# design.net
KiCad netlist of a schematic drawn in Altium Designer
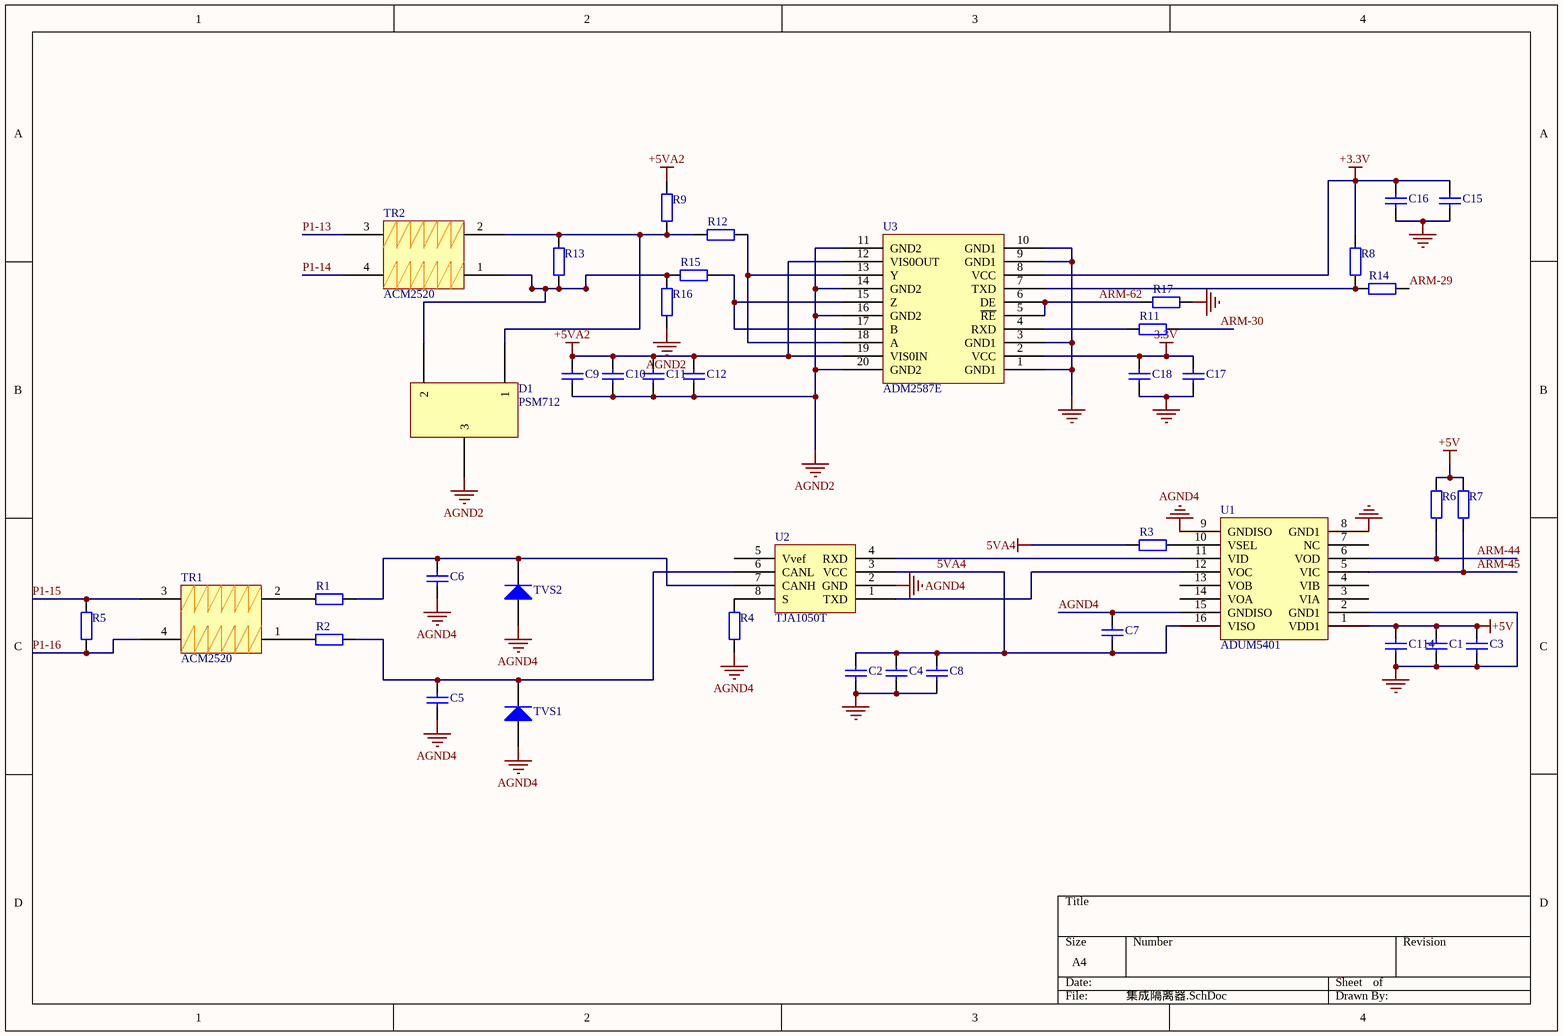
[diagram p0: 集成隔离器.SchDoc]

(export (version "E")
  (design (tool "Eeschema 10.0.6"))
  (components
    (comp (ref "C1")
      (value "Cap")
      (footprint "RAD-0.3")
      (description "Capacitor")
      (fields (field (name "PUBLISHER") "Altium Limited"))
      (libsource (lib "Miscellaneous Devices") (part "Cap"))
    )
    (comp (ref "C2")
      (value "Cap")
      (footprint "RAD-0.3")
      (description "Capacitor")
      (fields (field (name "PUBLISHER") "Altium Limited"))
      (libsource (lib "Miscellaneous Devices") (part "Cap"))
    )
    (comp (ref "C3")
      (value "Cap")
      (footprint "RAD-0.3")
      (description "Capacitor")
      (fields (field (name "PUBLISHER") "Altium Limited"))
      (libsource (lib "Miscellaneous Devices") (part "Cap"))
    )
    (comp (ref "C4")
      (value "Cap")
      (footprint "RAD-0.3")
      (description "Capacitor")
      (fields (field (name "PUBLISHER") "Altium Limited"))
      (libsource (lib "Miscellaneous Devices") (part "Cap"))
    )
    (comp (ref "C5")
      (value "Cap")
      (footprint "RAD-0.3")
      (description "Capacitor")
      (fields (field (name "PUBLISHER") "Altium Limited"))
      (libsource (lib "Miscellaneous Devices") (part "Cap"))
    )
    (comp (ref "C6")
      (value "Cap")
      (footprint "RAD-0.3")
      (description "Capacitor")
      (fields (field (name "PUBLISHER") "Altium Limited"))
      (libsource (lib "Miscellaneous Devices") (part "Cap"))
    )
    (comp (ref "C7")
      (value "Cap")
      (footprint "RAD-0.3")
      (description "Capacitor")
      (fields (field (name "PUBLISHER") "Altium Limited"))
      (libsource (lib "Miscellaneous Devices") (part "Cap"))
    )
    (comp (ref "C8")
      (value "Cap")
      (footprint "RAD-0.3")
      (description "Capacitor")
      (fields (field (name "PUBLISHER") "Altium Limited"))
      (libsource (lib "Miscellaneous Devices") (part "Cap"))
    )
    (comp (ref "C9")
      (value "Cap")
      (footprint "RAD-0.3")
      (description "Capacitor")
      (fields (field (name "PUBLISHER") "Altium Limited"))
      (libsource (lib "Miscellaneous Devices") (part "Cap"))
    )
    (comp (ref "C10")
      (value "Cap")
      (footprint "RAD-0.3")
      (description "Capacitor")
      (fields (field (name "PUBLISHER") "Altium Limited"))
      (libsource (lib "Miscellaneous Devices") (part "Cap"))
    )
    (comp (ref "C11")
      (value "Cap")
      (footprint "RAD-0.3")
      (description "Capacitor")
      (fields (field (name "PUBLISHER") "Altium Limited"))
      (libsource (lib "Miscellaneous Devices") (part "Cap"))
    )
    (comp (ref "C12")
      (value "Cap")
      (footprint "RAD-0.3")
      (description "Capacitor")
      (fields (field (name "PUBLISHER") "Altium Limited"))
      (libsource (lib "Miscellaneous Devices") (part "Cap"))
    )
    (comp (ref "C15")
      (value "Cap")
      (footprint "RAD-0.3")
      (description "Capacitor")
      (fields (field (name "PUBLISHER") "Altium Limited"))
      (libsource (lib "Miscellaneous Devices") (part "Cap"))
    )
    (comp (ref "C16")
      (value "Cap")
      (footprint "RAD-0.3")
      (description "Capacitor")
      (fields (field (name "PUBLISHER") "Altium Limited"))
      (libsource (lib "Miscellaneous Devices") (part "Cap"))
    )
    (comp (ref "C17")
      (value "Cap")
      (footprint "RAD-0.3")
      (description "Capacitor")
      (fields (field (name "PUBLISHER") "Altium Limited"))
      (libsource (lib "Miscellaneous Devices") (part "Cap"))
    )
    (comp (ref "C18")
      (value "Cap")
      (footprint "RAD-0.3")
      (description "Capacitor")
      (fields (field (name "PUBLISHER") "Altium Limited"))
      (libsource (lib "Miscellaneous Devices") (part "Cap"))
    )
    (comp (ref "C114")
      (value "Cap")
      (footprint "RAD-0.3")
      (description "Capacitor")
      (fields (field (name "PUBLISHER") "Altium Limited"))
      (libsource (lib "Miscellaneous Devices") (part "Cap"))
    )
    (comp (ref "D1") (value "PSM712") (libsource (lib "标准电容阵列") (part "Component_1")))
    (comp (ref "R1")
      (value "Res2")
      (footprint "AXIAL-0.4")
      (description "Resistor")
      (fields (field (name "PUBLISHER") "Altium Limited"))
      (libsource (lib "Miscellaneous Devices") (part "Res2"))
    )
    (comp (ref "R2")
      (value "Res2")
      (footprint "AXIAL-0.4")
      (description "Resistor")
      (fields (field (name "PUBLISHER") "Altium Limited"))
      (libsource (lib "Miscellaneous Devices") (part "Res2"))
    )
    (comp (ref "R3")
      (value "Res2")
      (footprint "AXIAL-0.4")
      (description "Resistor")
      (fields (field (name "PUBLISHER") "Altium Limited"))
      (libsource (lib "") (part "Res2_3"))
    )
    (comp (ref "R4")
      (value "Res2")
      (footprint "AXIAL-0.4")
      (description "Resistor")
      (fields (field (name "PUBLISHER") "Altium Limited"))
      (libsource (lib "") (part "Res2_2"))
    )
    (comp (ref "R5")
      (value "Res2")
      (footprint "AXIAL-0.4")
      (description "Resistor")
      (fields (field (name "PUBLISHER") "Altium Limited"))
      (libsource (lib "") (part "Res2_1"))
    )
    (comp (ref "R6")
      (value "Res2")
      (footprint "AXIAL-0.4")
      (description "Resistor")
      (fields (field (name "PUBLISHER") "Altium Limited"))
      (libsource (lib "") (part "Res2_1"))
    )
    (comp (ref "R7")
      (value "Res2")
      (footprint "AXIAL-0.4")
      (description "Resistor")
      (fields (field (name "PUBLISHER") "Altium Limited"))
      (libsource (lib "") (part "Res2_1"))
    )
    (comp (ref "R8")
      (value "Res2")
      (footprint "AXIAL-0.4")
      (description "Resistor")
      (fields (field (name "PUBLISHER") "Altium Limited"))
      (libsource (lib "") (part "Res2_2"))
    )
    (comp (ref "R9")
      (value "Res2")
      (footprint "AXIAL-0.4")
      (description "Resistor")
      (fields (field (name "PUBLISHER") "Altium Limited"))
      (libsource (lib "") (part "Res2_1"))
    )
    (comp (ref "R11")
      (value "Res2")
      (footprint "AXIAL-0.4")
      (description "Resistor")
      (fields (field (name "PUBLISHER") "Altium Limited"))
      (libsource (lib "Miscellaneous Devices") (part "Res2"))
    )
    (comp (ref "R12")
      (value "Res2")
      (footprint "AXIAL-0.4")
      (description "Resistor")
      (fields (field (name "PUBLISHER") "Altium Limited"))
      (libsource (lib "Miscellaneous Devices") (part "Res2"))
    )
    (comp (ref "R13")
      (value "Res2")
      (footprint "AXIAL-0.4")
      (description "Resistor")
      (fields (field (name "PUBLISHER") "Altium Limited"))
      (libsource (lib "") (part "Res2_1"))
    )
    (comp (ref "R14")
      (value "Res2")
      (footprint "AXIAL-0.4")
      (description "Resistor")
      (fields (field (name "PUBLISHER") "Altium Limited"))
      (libsource (lib "") (part "Res2_3"))
    )
    (comp (ref "R15")
      (value "Res2")
      (footprint "AXIAL-0.4")
      (description "Resistor")
      (fields (field (name "PUBLISHER") "Altium Limited"))
      (libsource (lib "Miscellaneous Devices") (part "Res2"))
    )
    (comp (ref "R16")
      (value "Res2")
      (footprint "AXIAL-0.4")
      (description "Resistor")
      (fields (field (name "PUBLISHER") "Altium Limited"))
      (libsource (lib "") (part "Res2_1"))
    )
    (comp (ref "R17")
      (value "Res2")
      (footprint "AXIAL-0.4")
      (description "Resistor")
      (fields (field (name "PUBLISHER") "Altium Limited"))
      (libsource (lib "Miscellaneous Devices") (part "Res2"))
    )
    (comp (ref "TR1") (value "ACM2520") (libsource (lib "ACM共模电感") (part "Component_1")))
    (comp (ref "TR2") (value "ACM2520") (libsource (lib "ACM共模电感") (part "Component_1")))
    (comp (ref "TVS1")
      (value "Diode 1N4007")
      (footprint "DO-41")
      (description "1 Amp General Purpose Rectifier")
      (fields (field (name "PUBLISHER") "Altium Limited"))
      (libsource (lib "Miscellaneous Devices") (part "Diode 1N4007"))
    )
    (comp (ref "TVS2")
      (value "Diode 1N4007")
      (footprint "DO-41")
      (description "1 Amp General Purpose Rectifier")
      (fields (field (name "PUBLISHER") "Altium Limited"))
      (libsource (lib "Miscellaneous Devices") (part "Diode 1N4007"))
    )
    (comp (ref "U1") (value "ADUM5401") (libsource (lib "ADUM5401") (part "Component_1")))
    (comp (ref "U2") (value "TJA1050T") (libsource (lib "TJA1050T") (part "Component_1")))
    (comp (ref "U3") (value "ADM2587E") (libsource (lib "ADM2587E") (part "Component_1")))
  )
  (nets
    (net (code "1") (name "+3.3V") (class "Default")
      (node (ref "C15") (pin "2") (pinfunction "2_2") (pintype "passive"))
      (node (ref "C16") (pin "2") (pinfunction "2_2") (pintype "passive"))
      (node (ref "R8") (pin "1") (pinfunction "1_1") (pintype "passive"))
      (node (ref "U3") (pin "8") (pinfunction "VCC_8") (pintype "passive"))
    )
    (net (code "2") (name "+5V") (class "Default")
      (node (ref "C1") (pin "2") (pinfunction "2_2") (pintype "passive"))
      (node (ref "C114") (pin "2") (pinfunction "2_2") (pintype "passive"))
      (node (ref "C3") (pin "2") (pinfunction "2_2") (pintype "passive"))
      (node (ref "R6") (pin "2") (pinfunction "2_2") (pintype "passive"))
      (node (ref "R7") (pin "2") (pinfunction "2_2") (pintype "passive"))
      (node (ref "U1") (pin "1") (pinfunction "VDD1_1") (pintype "passive"))
    )
    (net (code "3") (name "+5VA2") (class "Default")
      (node (ref "C10") (pin "2") (pinfunction "2_2") (pintype "passive"))
      (node (ref "C11") (pin "2") (pinfunction "2_2") (pintype "passive"))
      (node (ref "C12") (pin "2") (pinfunction "2_2") (pintype "passive"))
      (node (ref "C9") (pin "2") (pinfunction "2_2") (pintype "passive"))
      (node (ref "R9") (pin "2") (pinfunction "2_2") (pintype "passive"))
      (node (ref "U3") (pin "12") (pinfunction "VIS0OUT_12") (pintype "passive"))
      (node (ref "U3") (pin "19") (pinfunction "VIS0IN_19") (pintype "passive"))
    )
    (net (code "4") (name "/ARM-29") (class "Default")
      (node (ref "R14") (pin "2") (pinfunction "2_2") (pintype "passive"))
    )
    (net (code "5") (name "/ARM-30") (class "Default")
      (node (ref "R11") (pin "1") (pinfunction "1_1") (pintype "passive"))
    )
    (net (code "6") (name "/ARM-44") (class "Default")
      (node (ref "R6") (pin "1") (pinfunction "1_1") (pintype "passive"))
      (node (ref "U1") (pin "6") (pinfunction "VOD_6") (pintype "passive"))
    )
    (net (code "7") (name "/ARM-45") (class "Default")
      (node (ref "R7") (pin "1") (pinfunction "1_1") (pintype "passive"))
      (node (ref "U1") (pin "5") (pinfunction "VIC_5") (pintype "passive"))
    )
    (net (code "8") (name "/ARM-62") (class "Default")
      (node (ref "R17") (pin "2") (pinfunction "2_2") (pintype "passive"))
      (node (ref "U3") (pin "5") (pinfunction "~{RE}_5") (pintype "passive"))
      (node (ref "U3") (pin "6") (pinfunction "DE_6") (pintype "passive"))
    )
    (net (code "9") (name "/P1-13") (class "Default")
      (node (ref "TR2") (pin "3") (pinfunction "0_3") (pintype "passive"))
    )
    (net (code "10") (name "/P1-14") (class "Default")
      (node (ref "TR2") (pin "4") (pinfunction "4_4") (pintype "passive"))
    )
    (net (code "11") (name "/P1-15") (class "Default")
      (node (ref "R5") (pin "2") (pinfunction "2_2") (pintype "passive"))
      (node (ref "TR1") (pin "3") (pinfunction "0_3") (pintype "passive"))
    )
    (net (code "12") (name "/P1-16") (class "Default")
      (node (ref "R5") (pin "1") (pinfunction "1_1") (pintype "passive"))
      (node (ref "TR1") (pin "4") (pinfunction "4_4") (pintype "passive"))
    )
    (net (code "13") (name "3.3V") (class "Default")
      (node (ref "C17") (pin "2") (pinfunction "2_2") (pintype "passive"))
      (node (ref "C18") (pin "2") (pinfunction "2_2") (pintype "passive"))
      (node (ref "U3") (pin "2") (pinfunction "VCC_2") (pintype "passive"))
    )
    (net (code "14") (name "5VA4") (class "Default")
      (node (ref "C2") (pin "2") (pinfunction "2_2") (pintype "passive"))
      (node (ref "C4") (pin "2") (pinfunction "2_2") (pintype "passive"))
      (node (ref "C7") (pin "1") (pinfunction "1_1") (pintype "passive"))
      (node (ref "C8") (pin "2") (pinfunction "2_2") (pintype "passive"))
      (node (ref "R3") (pin "1") (pinfunction "1_1") (pintype "passive"))
      (node (ref "U1") (pin "16") (pinfunction "VISO_16") (pintype "passive"))
      (node (ref "U2") (pin "3") (pinfunction "VCC_3") (pintype "passive"))
    )
    (net (code "15") (name "AGND2") (class "Default")
      (node (ref "C10") (pin "1") (pinfunction "1_1") (pintype "passive"))
      (node (ref "C11") (pin "1") (pinfunction "1_1") (pintype "passive"))
      (node (ref "C12") (pin "1") (pinfunction "1_1") (pintype "passive"))
      (node (ref "C9") (pin "1") (pinfunction "1_1") (pintype "passive"))
      (node (ref "D1") (pin "3") (pinfunction "3_3") (pintype "passive"))
      (node (ref "R16") (pin "1") (pinfunction "1_1") (pintype "passive"))
      (node (ref "U3") (pin "11") (pinfunction "GND2_11") (pintype "passive"))
      (node (ref "U3") (pin "14") (pinfunction "GND2_14") (pintype "passive"))
      (node (ref "U3") (pin "16") (pinfunction "GND2_16") (pintype "passive"))
      (node (ref "U3") (pin "20") (pinfunction "GND2_20") (pintype "passive"))
    )
    (net (code "16") (name "AGND4") (class "Default")
      (node (ref "C5") (pin "1") (pinfunction "1_1") (pintype "passive"))
      (node (ref "C6") (pin "1") (pinfunction "1_1") (pintype "passive"))
      (node (ref "C7") (pin "2") (pinfunction "2_2") (pintype "passive"))
      (node (ref "R4") (pin "2") (pinfunction "2_2") (pintype "passive"))
      (node (ref "TVS1") (pin "1") (pinfunction "A_1") (pintype "passive"))
      (node (ref "TVS2") (pin "1") (pinfunction "A_1") (pintype "passive"))
      (node (ref "U1") (pin "15") (pinfunction "GNDISO_15") (pintype "passive"))
      (node (ref "U1") (pin "9") (pinfunction "GNDISO_9") (pintype "passive"))
      (node (ref "U2") (pin "2") (pinfunction "GND_2") (pintype "passive"))
    )
    (net (code "17") (name "GND") (class "Default")
      (node (ref "C1") (pin "1") (pinfunction "1_1") (pintype "passive"))
      (node (ref "C114") (pin "1") (pinfunction "1_1") (pintype "passive"))
      (node (ref "C15") (pin "1") (pinfunction "1_1") (pintype "passive"))
      (node (ref "C16") (pin "1") (pinfunction "1_1") (pintype "passive"))
      (node (ref "C17") (pin "1") (pinfunction "1_1") (pintype "passive"))
      (node (ref "C18") (pin "1") (pinfunction "1_1") (pintype "passive"))
      (node (ref "C2") (pin "1") (pinfunction "1_1") (pintype "passive"))
      (node (ref "C3") (pin "1") (pinfunction "1_1") (pintype "passive"))
      (node (ref "C4") (pin "1") (pinfunction "1_1") (pintype "passive"))
      (node (ref "C8") (pin "1") (pinfunction "1_1") (pintype "passive"))
      (node (ref "R17") (pin "1") (pinfunction "1_1") (pintype "passive"))
      (node (ref "U1") (pin "2") (pinfunction "GND1_2") (pintype "passive"))
      (node (ref "U1") (pin "8") (pinfunction "GND1_8") (pintype "passive"))
      (node (ref "U3") (pin "1") (pinfunction "GND1_1") (pintype "passive"))
      (node (ref "U3") (pin "10") (pinfunction "GND1_10") (pintype "passive"))
      (node (ref "U3") (pin "3") (pinfunction "GND1_3") (pintype "passive"))
      (node (ref "U3") (pin "9") (pinfunction "GND1_9") (pintype "passive"))
    )
    (net (code "18") (name "Net-(D1-2)") (class "Default")
      (node (ref "D1") (pin "0") (pinfunction "2_0") (pintype "passive"))
      (node (ref "R13") (pin "1") (pinfunction "1_1") (pintype "passive"))
      (node (ref "R15") (pin "2") (pinfunction "2_2") (pintype "passive"))
      (node (ref "R16") (pin "2") (pinfunction "2_2") (pintype "passive"))
      (node (ref "TR2") (pin "1") (pinfunction "3_1") (pintype "passive"))
    )
    (net (code "19") (name "Net-(D1-Pad1)") (class "Default")
      (node (ref "D1") (pin "1") (pinfunction "1_1") (pintype "passive"))
      (node (ref "R12") (pin "2") (pinfunction "2_2") (pintype "passive"))
      (node (ref "R13") (pin "2") (pinfunction "2_2") (pintype "passive"))
      (node (ref "R9") (pin "1") (pinfunction "1_1") (pintype "passive"))
      (node (ref "TR2") (pin "2") (pinfunction "2_2") (pintype "passive"))
    )
    (net (code "20") (name "Net-(R1-Pad2)") (class "Default")
      (node (ref "R1") (pin "2") (pinfunction "2_2") (pintype "passive"))
      (node (ref "TR1") (pin "2") (pinfunction "2_2") (pintype "passive"))
    )
    (net (code "21") (name "Net-(TR1-3)") (class "Default")
      (node (ref "R2") (pin "2") (pinfunction "2_2") (pintype "passive"))
      (node (ref "TR1") (pin "1") (pinfunction "3_1") (pintype "passive"))
    )
    (net (code "22") (name "Net-(TVS1-K)") (class "Default")
      (node (ref "C5") (pin "2") (pinfunction "2_2") (pintype "passive"))
      (node (ref "R2") (pin "1") (pinfunction "1_1") (pintype "passive"))
      (node (ref "TVS1") (pin "2") (pinfunction "K_2") (pintype "passive"))
      (node (ref "U2") (pin "6") (pinfunction "CANL_6") (pintype "passive"))
    )
    (net (code "23") (name "Net-(TVS2-K)") (class "Default")
      (node (ref "C6") (pin "2") (pinfunction "2_2") (pintype "passive"))
      (node (ref "R1") (pin "1") (pinfunction "1_1") (pintype "passive"))
      (node (ref "TVS2") (pin "2") (pinfunction "K_2") (pintype "passive"))
      (node (ref "U2") (pin "7") (pinfunction "CANH_7") (pintype "passive"))
    )
    (net (code "24") (name "Net-(U1-VID)") (class "Default")
      (node (ref "U1") (pin "11") (pinfunction "VID_11") (pintype "passive"))
      (node (ref "U2") (pin "4") (pinfunction "RXD_4") (pintype "passive"))
    )
    (net (code "25") (name "Net-(U1-VOC)") (class "Default")
      (node (ref "U1") (pin "12") (pinfunction "VOC_12") (pintype "passive"))
      (node (ref "U2") (pin "1") (pinfunction "TXD_1") (pintype "passive"))
    )
    (net (code "26") (name "Net-(U1-VSEL)") (class "Default")
      (node (ref "R3") (pin "2") (pinfunction "2_2") (pintype "passive"))
      (node (ref "U1") (pin "10") (pinfunction "VSEL_10") (pintype "passive"))
    )
    (net (code "27") (name "Net-(U2-S)") (class "Default")
      (node (ref "R4") (pin "1") (pinfunction "1_1") (pintype "passive"))
      (node (ref "U2") (pin "8") (pinfunction "S_8") (pintype "passive"))
    )
    (net (code "28") (name "Net-(U3-A)") (class "Default")
      (node (ref "R12") (pin "1") (pinfunction "1_1") (pintype "passive"))
      (node (ref "U3") (pin "13") (pinfunction "Y_13") (pintype "passive"))
      (node (ref "U3") (pin "18") (pinfunction "A_18") (pintype "passive"))
    )
    (net (code "29") (name "Net-(U3-B)") (class "Default")
      (node (ref "R15") (pin "1") (pinfunction "1_1") (pintype "passive"))
      (node (ref "U3") (pin "15") (pinfunction "Z_15") (pintype "passive"))
      (node (ref "U3") (pin "17") (pinfunction "B_17") (pintype "passive"))
    )
    (net (code "30") (name "Net-(U3-RXD)") (class "Default")
      (node (ref "R11") (pin "2") (pinfunction "2_2") (pintype "passive"))
      (node (ref "U3") (pin "4") (pinfunction "RXD_4") (pintype "passive"))
    )
    (net (code "31") (name "Net-(U3-TXD)") (class "Default")
      (node (ref "R14") (pin "1") (pinfunction "1_1") (pintype "passive"))
      (node (ref "R8") (pin "2") (pinfunction "2_2") (pintype "passive"))
      (node (ref "U3") (pin "7") (pinfunction "TXD_7") (pintype "passive"))
    )
    (net (code "32") (name "unconnected-(U1-NC-Pad7)") (class "Default")
      (node (ref "U1") (pin "7") (pinfunction "NC_7") (pintype "passive"))
    )
    (net (code "33") (name "unconnected-(U1-VIA-Pad3)") (class "Default")
      (node (ref "U1") (pin "3") (pinfunction "VIA_3") (pintype "passive"))
    )
    (net (code "34") (name "unconnected-(U1-VIB-Pad4)") (class "Default")
      (node (ref "U1") (pin "4") (pinfunction "VIB_4") (pintype "passive"))
    )
    (net (code "35") (name "unconnected-(U1-VOA-Pad14)") (class "Default")
      (node (ref "U1") (pin "14") (pinfunction "VOA_14") (pintype "passive"))
    )
    (net (code "36") (name "unconnected-(U1-VOB-Pad13)") (class "Default")
      (node (ref "U1") (pin "13") (pinfunction "VOB_13") (pintype "passive"))
    )
    (net (code "37") (name "unconnected-(U2-Vvef-Pad5)") (class "Default")
      (node (ref "U2") (pin "5") (pinfunction "Vvef_5") (pintype "passive"))
    )
  )
)
